# MastModule_v8.net
KiCad netlist of a schematic drawn in EAGLE
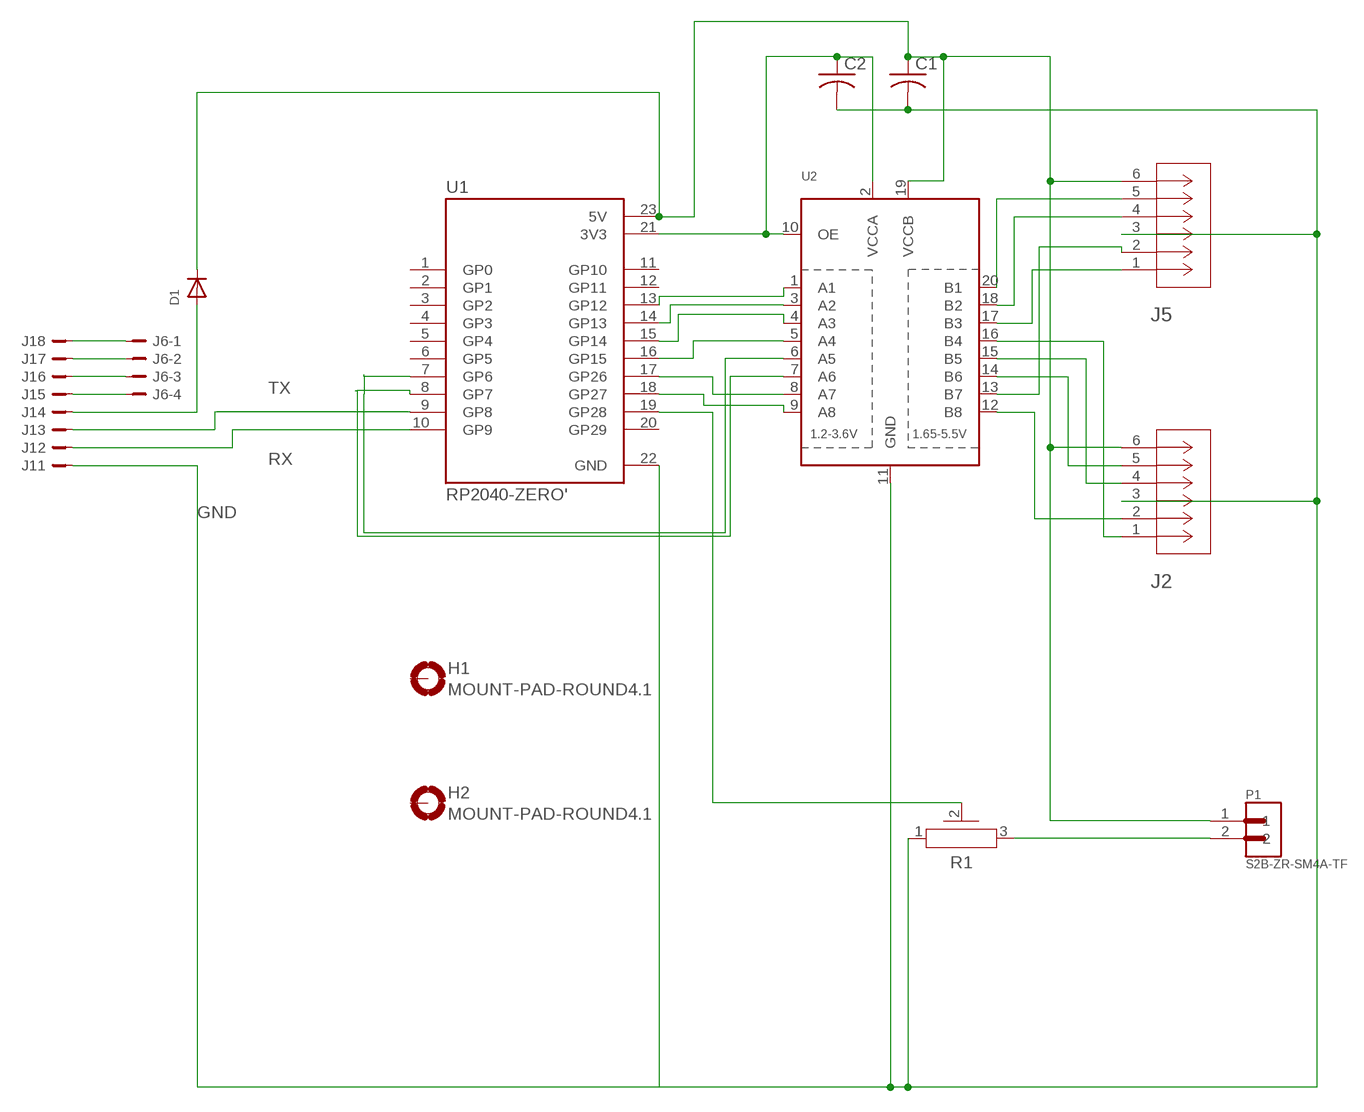
[diagram p0: schematic, sheet 1]

(export (version "E")
  (design (tool "Eeschema 10.0.6"))
  (components
    (comp (ref "C1")
      (value "C-USC1210")
      (footprint "eagle-import:C1210")
      (libsource (lib "eagle-import") (part "C-USC1210"))
    )
    (comp (ref "C2")
      (value "C-USC1210")
      (footprint "eagle-import:C1210")
      (libsource (lib "eagle-import") (part "C-USC1210"))
    )
    (comp (ref "D1")
      (value "DIODESMA")
      (footprint "eagle-import:SMADIODE")
      (libsource (lib "eagle-import") (part "DIODESMA"))
    )
    (comp (ref "H1")
      (value "MOUNT-PAD-ROUND4.1")
      (footprint "eagle-import:4,1-PAD")
      (libsource (lib "eagle-import") (part "MOUNT-PAD-ROUND4.1"))
    )
    (comp (ref "H2")
      (value "MOUNT-PAD-ROUND4.1")
      (footprint "eagle-import:4,1-PAD")
      (libsource (lib "eagle-import") (part "MOUNT-PAD-ROUND4.1"))
    )
    (comp (ref "J1")
      (value "B8B-PH-K-S")
      (footprint "eagle-import:B8B-PH-K-S")
      (libsource (lib "eagle-import") (part "B8B-PH-K-S"))
    )
    (comp (ref "J2")
      (value "2132260630CONN_2132260000-SD_06_MOL")
      (footprint "eagle-import:CONN_2132260000-SD_06_MOL")
      (fields
        (field (name "MANUFACTURER_PART_NUMBER") "2132260630")
        (field (name "COPYRIGHT") "Copyright (C) 2025 Ultra Librarian. All rights reserved.")
      )
      (libsource (lib "eagle-import") (part "2132260630CONN_2132260000-SD_06_MOL"))
    )
    (comp (ref "J5")
      (value "2132260630CONN_2132260000-SD_06_MOL")
      (footprint "eagle-import:CONN_2132260000-SD_06_MOL")
      (fields
        (field (name "MANUFACTURER_PART_NUMBER") "2132260630")
        (field (name "COPYRIGHT") "Copyright (C) 2025 Ultra Librarian. All rights reserved.")
      )
      (libsource (lib "eagle-import") (part "2132260630CONN_2132260000-SD_06_MOL"))
    )
    (comp (ref "J6")
      (value "JST-PH-4_TH-RA")
      (footprint "eagle-import:S4B-PH-KL")
      (fields (field (name "MF") "JST") (field (name "MPN") "S4B-PH-KL"))
      (libsource (lib "eagle-import") (part "JST-PH-4_TH-RA"))
    )
    (comp (ref "P1")
      (value "S2B-ZR-SM4A-TF")
      (footprint "eagle-import:JST_S2B-ZR-SM4A-TF")
      (fields (field (name "MF") "JST Sales"))
      (libsource (lib "eagle-import") (part "S2B-ZR-SM4A-TF"))
    )
    (comp (ref "R1")
      (value "PV36X")
      (footprint "eagle-import:PV36X")
      (fields
        (field (name "MANUFACTURER") "Bourns Inc.")
        (field (name "MPN") "PV36Xx")
        (field (name "TOLERANCE") "±10%")
      )
      (libsource (lib "eagle-import") (part "PV36X"))
    )
    (comp (ref "U1")
      (value "RP2040-ZERO'")
      (footprint "eagle-import:MODULE_RP2040-ZERO")
      (fields (field (name "MF") "Waveshare Electronics") (field (name "MP") "RP2040-ZERO"))
      (libsource (lib "eagle-import") (part "RP2040-ZERO'"))
    )
    (comp (ref "U2")
      (value "TXB0108PWR")
      (footprint "eagle-import:TSSOP20")
      (libsource (lib "eagle-import") (part "TXB0108PWR"))
    )
  )
  (nets
    (net (code "1") (name "/GND") (class "Default")
      (node (ref "C1") (pin "2") (pinfunction "2_2") (pintype "passive"))
      (node (ref "C2") (pin "2") (pinfunction "2_2") (pintype "passive"))
      (node (ref "J1") (pin "1") (pinfunction "1_1") (pintype "passive"))
      (node (ref "J2") (pin "3") (pinfunction "3_3") (pintype "passive"))
      (node (ref "J5") (pin "3") (pinfunction "3_3") (pintype "passive"))
      (node (ref "R1") (pin "1") (pinfunction "P$1_1") (pintype "passive"))
      (node (ref "U1") (pin "22") (pinfunction "GND_22") (pintype "power_in"))
      (node (ref "U2") (pin "11") (pinfunction "GND_11") (pintype "bidirectional"))
    )
    (net (code "2") (name "/RX") (class "Default")
      (node (ref "J1") (pin "2") (pinfunction "1_2") (pintype "passive"))
      (node (ref "U1") (pin "10") (pinfunction "GP9_10") (pintype "bidirectional"))
    )
    (net (code "3") (name "/TX") (class "Default")
      (node (ref "J1") (pin "3") (pinfunction "1_3") (pintype "passive"))
      (node (ref "U1") (pin "9") (pinfunction "GP8_9") (pintype "bidirectional"))
    )
    (net (code "4") (name "Net-(J1D-1)") (class "Default")
      (node (ref "D1") (pin "A") (pinfunction "A_A") (pintype "passive"))
      (node (ref "J1") (pin "4") (pinfunction "1_4") (pintype "passive"))
    )
    (net (code "5") (name "Net-(J1E-1)") (class "Default")
      (node (ref "J1") (pin "5") (pinfunction "1_5") (pintype "passive"))
      (node (ref "J6") (pin "4") (pinfunction "1_4") (pintype "passive"))
    )
    (net (code "6") (name "Net-(J1F-1)") (class "Default")
      (node (ref "J1") (pin "6") (pinfunction "1_6") (pintype "passive"))
      (node (ref "J6") (pin "3") (pinfunction "1_3") (pintype "passive"))
    )
    (net (code "7") (name "Net-(J1G-1)") (class "Default")
      (node (ref "J1") (pin "7") (pinfunction "1_7") (pintype "passive"))
      (node (ref "J6") (pin "2") (pinfunction "1_2") (pintype "passive"))
    )
    (net (code "8") (name "Net-(J1H-1)") (class "Default")
      (node (ref "J1") (pin "8") (pinfunction "1_8") (pintype "passive"))
      (node (ref "J6") (pin "1") (pinfunction "1_1") (pintype "passive"))
    )
    (net (code "9") (name "Net-(R1-P$2)") (class "Default")
      (node (ref "R1") (pin "2") (pinfunction "P$2_2") (pintype "passive"))
      (node (ref "U1") (pin "19") (pinfunction "GP28_19") (pintype "bidirectional"))
    )
    (net (code "10") (name "Net-(R1-P$3)") (class "Default")
      (node (ref "P1") (pin "2") (pinfunction "2_2") (pintype "passive"))
      (node (ref "R1") (pin "3") (pinfunction "P$3_3") (pintype "passive"))
    )
    (net (code "11") (name "Net-(U1-3V3)") (class "Default")
      (node (ref "C2") (pin "1") (pinfunction "1_1") (pintype "passive"))
      (node (ref "U1") (pin "21") (pinfunction "3V3_21") (pintype "power_in"))
      (node (ref "U2") (pin "10") (pinfunction "OE_10") (pintype "bidirectional"))
      (node (ref "U2") (pin "2") (pinfunction "VCCA_2") (pintype "bidirectional"))
    )
    (net (code "12") (name "Net-(U1-5V)") (class "Default")
      (node (ref "C1") (pin "1") (pinfunction "1_1") (pintype "passive"))
      (node (ref "D1") (pin "C") (pinfunction "C_C") (pintype "passive"))
      (node (ref "J2") (pin "6") (pinfunction "6_6") (pintype "passive"))
      (node (ref "J5") (pin "6") (pinfunction "6_6") (pintype "passive"))
      (node (ref "P1") (pin "1") (pinfunction "1_1") (pintype "passive"))
      (node (ref "U1") (pin "23") (pinfunction "5V_23") (pintype "power_in"))
      (node (ref "U2") (pin "19") (pinfunction "VCCB_19") (pintype "bidirectional"))
    )
    (net (code "13") (name "Net-(U1-GP6)") (class "Default")
      (node (ref "U1") (pin "7") (pinfunction "GP6_7") (pintype "bidirectional"))
      (node (ref "U2") (pin "6") (pinfunction "A5_6") (pintype "bidirectional"))
    )
    (net (code "14") (name "Net-(U1-GP7)") (class "Default")
      (node (ref "U1") (pin "8") (pinfunction "GP7_8") (pintype "bidirectional"))
      (node (ref "U2") (pin "7") (pinfunction "A6_7") (pintype "bidirectional"))
    )
    (net (code "15") (name "Net-(U1-GP12)") (class "Default")
      (node (ref "U1") (pin "13") (pinfunction "GP12_13") (pintype "bidirectional"))
      (node (ref "U2") (pin "1") (pinfunction "A1_1") (pintype "bidirectional"))
    )
    (net (code "16") (name "Net-(U1-GP13)") (class "Default")
      (node (ref "U1") (pin "14") (pinfunction "GP13_14") (pintype "bidirectional"))
      (node (ref "U2") (pin "3") (pinfunction "A2_3") (pintype "bidirectional"))
    )
    (net (code "17") (name "Net-(U1-GP14)") (class "Default")
      (node (ref "U1") (pin "15") (pinfunction "GP14_15") (pintype "bidirectional"))
      (node (ref "U2") (pin "4") (pinfunction "A3_4") (pintype "bidirectional"))
    )
    (net (code "18") (name "Net-(U1-GP15)") (class "Default")
      (node (ref "U1") (pin "16") (pinfunction "GP15_16") (pintype "bidirectional"))
      (node (ref "U2") (pin "5") (pinfunction "A4_5") (pintype "bidirectional"))
    )
    (net (code "19") (name "Net-(U1-GP26)") (class "Default")
      (node (ref "U1") (pin "17") (pinfunction "GP26_17") (pintype "bidirectional"))
      (node (ref "U2") (pin "8") (pinfunction "A7_8") (pintype "bidirectional"))
    )
    (net (code "20") (name "Net-(U1-GP27)") (class "Default")
      (node (ref "U1") (pin "18") (pinfunction "GP27_18") (pintype "bidirectional"))
      (node (ref "U2") (pin "9") (pinfunction "A8_9") (pintype "bidirectional"))
    )
    (net (code "21") (name "Net-(U2-B1)") (class "Default")
      (node (ref "J5") (pin "5") (pinfunction "5_5") (pintype "passive"))
      (node (ref "U2") (pin "20") (pinfunction "B1_20") (pintype "bidirectional"))
    )
    (net (code "22") (name "Net-(U2-B2)") (class "Default")
      (node (ref "J5") (pin "4") (pinfunction "4_4") (pintype "passive"))
      (node (ref "U2") (pin "18") (pinfunction "B2_18") (pintype "bidirectional"))
    )
    (net (code "23") (name "Net-(U2-B3)") (class "Default")
      (node (ref "J5") (pin "1") (pinfunction "1_1") (pintype "passive"))
      (node (ref "U2") (pin "17") (pinfunction "B3_17") (pintype "bidirectional"))
    )
    (net (code "24") (name "Net-(U2-B4)") (class "Default")
      (node (ref "J2") (pin "1") (pinfunction "1_1") (pintype "passive"))
      (node (ref "U2") (pin "16") (pinfunction "B4_16") (pintype "bidirectional"))
    )
    (net (code "25") (name "Net-(U2-B5)") (class "Default")
      (node (ref "J2") (pin "4") (pinfunction "4_4") (pintype "passive"))
      (node (ref "U2") (pin "15") (pinfunction "B5_15") (pintype "bidirectional"))
    )
    (net (code "26") (name "Net-(U2-B6)") (class "Default")
      (node (ref "J2") (pin "5") (pinfunction "5_5") (pintype "passive"))
      (node (ref "U2") (pin "14") (pinfunction "B6_14") (pintype "bidirectional"))
    )
    (net (code "27") (name "Net-(U2-B7)") (class "Default")
      (node (ref "J5") (pin "2") (pinfunction "2_2") (pintype "passive"))
      (node (ref "U2") (pin "13") (pinfunction "B7_13") (pintype "bidirectional"))
    )
    (net (code "28") (name "Net-(U2-B8)") (class "Default")
      (node (ref "J2") (pin "2") (pinfunction "2_2") (pintype "passive"))
      (node (ref "U2") (pin "12") (pinfunction "B8_12") (pintype "bidirectional"))
    )
    (net (code "29") (name "unconnected-(H1-MOUNT-PadB4,1)") (class "Default")
      (node (ref "H1") (pin "B4,1") (pinfunction "MOUNT_B4,1") (pintype "passive"))
    )
    (net (code "30") (name "unconnected-(H2-MOUNT-PadB4,1)") (class "Default")
      (node (ref "H2") (pin "B4,1") (pinfunction "MOUNT_B4,1") (pintype "passive"))
    )
    (net (code "31") (name "unconnected-(U1-GP0-Pad1)") (class "Default")
      (node (ref "U1") (pin "1") (pinfunction "GP0_1") (pintype "bidirectional"))
    )
    (net (code "32") (name "unconnected-(U1-GP1-Pad2)") (class "Default")
      (node (ref "U1") (pin "2") (pinfunction "GP1_2") (pintype "bidirectional"))
    )
    (net (code "33") (name "unconnected-(U1-GP2-Pad3)") (class "Default")
      (node (ref "U1") (pin "3") (pinfunction "GP2_3") (pintype "bidirectional"))
    )
    (net (code "34") (name "unconnected-(U1-GP3-Pad4)") (class "Default")
      (node (ref "U1") (pin "4") (pinfunction "GP3_4") (pintype "bidirectional"))
    )
    (net (code "35") (name "unconnected-(U1-GP4-Pad5)") (class "Default")
      (node (ref "U1") (pin "5") (pinfunction "GP4_5") (pintype "bidirectional"))
    )
    (net (code "36") (name "unconnected-(U1-GP5-Pad6)") (class "Default")
      (node (ref "U1") (pin "6") (pinfunction "GP5_6") (pintype "bidirectional"))
    )
    (net (code "37") (name "unconnected-(U1-GP10-Pad11)") (class "Default")
      (node (ref "U1") (pin "11") (pinfunction "GP10_11") (pintype "bidirectional"))
    )
    (net (code "38") (name "unconnected-(U1-GP11-Pad12)") (class "Default")
      (node (ref "U1") (pin "12") (pinfunction "GP11_12") (pintype "bidirectional"))
    )
    (net (code "39") (name "unconnected-(U1-GP29-Pad20)") (class "Default")
      (node (ref "U1") (pin "20") (pinfunction "GP29_20") (pintype "bidirectional"))
    )
  )
)
